# PowerSupply.net
KiCad netlist of a schematic drawn in Altium Designer
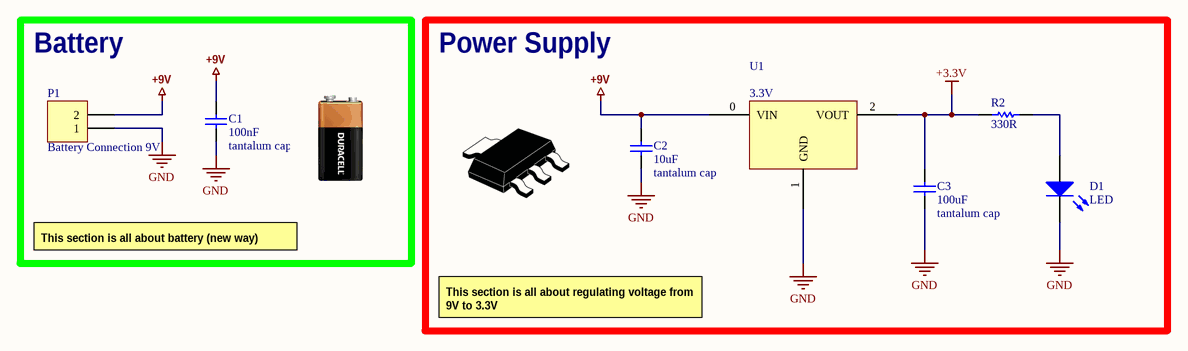
[diagram p0: PowerSupply.SchDoc]

(export (version "E")
  (design (tool "Eeschema 10.0.6"))
  (components
    (comp (ref "C1")
      (value "tantalum cap")
      (footprint "C1206tancap")
      (description "Capacitor (Semiconductor SIM Model)")
      (fields (field (name "ALTIUM_VALUE") "100nF") (field (name "PUBLISHER") "Altium Limited"))
      (libsource (lib "smartmcu") (part "Cap Semi_5"))
    )
    (comp (ref "C2")
      (value "tantalum cap")
      (footprint "C1206tancap")
      (description "Capacitor (Semiconductor SIM Model)")
      (fields (field (name "ALTIUM_VALUE") "10uF") (field (name "PUBLISHER") "Altium Limited"))
      (libsource (lib "smartmcu") (part "Cap Semi_5"))
    )
    (comp (ref "C3")
      (value "tantalum cap")
      (footprint "C1206tancap")
      (description "Capacitor (Semiconductor SIM Model)")
      (fields (field (name "ALTIUM_VALUE") "100uF") (field (name "PUBLISHER") "Altium Limited"))
      (libsource (lib "smartmcu") (part "Cap Semi_6"))
    )
    (comp (ref "D1")
      (value "LED")
      (footprint "MY_LED_0805")
      (description "Typical INFRARED GaAs LED")
      (fields (field (name "ASID PART NUMBER") "LED-AS"))
      (libsource (lib "Mylib+Rev+4") (part "LED"))
    )
    (comp (ref "P1")
      (value "Battery Connection 9V")
      (footprint "HDR1X2H3dbody")
      (description "Header, 2-Pin, Right Angle")
      (fields (field (name "VOLTAGE") "9V") (field (name "PUBLISHER") "Altium Limited"))
      (libsource (lib "smartmcu") (part "Header 2H"))
    )
    (comp (ref "R2")
      (value "330R")
      (footprint "MY_0805")
      (description "Standard resistor")
      (fields (field (name "ASID PART NUMBER") "Res-AS"))
      (libsource (lib "Mylib+Rev+4") (part "Res"))
    )
    (comp (ref "U1")
      (value "~")
      (footprint "4-Pin SOT")
      (fields (field (name "OUTPUT VOLTAGE") "3.3V"))
      (libsource (lib "smartmcu") (part "LM1117"))
    )
  )
  (nets
    (net (code "1") (name "+3.3V") (class "Default")
      (node (ref "C3") (pin "2") (pinfunction "2_2") (pintype "passive"))
      (node (ref "R2") (pin "1") (pinfunction "1_1") (pintype "passive"))
      (node (ref "U1") (pin "2") (pinfunction "VOUT_2") (pintype "passive"))
    )
    (net (code "2") (name "+9V") (class "Default")
      (node (ref "C1") (pin "2") (pinfunction "2_2") (pintype "passive"))
      (node (ref "C2") (pin "2") (pinfunction "2_2") (pintype "passive"))
      (node (ref "P1") (pin "2") (pinfunction "2_2") (pintype "passive"))
      (node (ref "U1") (pin "0") (pinfunction "VIN_0") (pintype "passive"))
    )
    (net (code "3") (name "GND") (class "Default")
      (node (ref "C1") (pin "1") (pinfunction "1_1") (pintype "passive"))
      (node (ref "C2") (pin "1") (pinfunction "1_1") (pintype "passive"))
      (node (ref "C3") (pin "1") (pinfunction "1_1") (pintype "passive"))
      (node (ref "D1") (pin "K") (pinfunction "K_K") (pintype "passive"))
      (node (ref "P1") (pin "1") (pinfunction "1_1") (pintype "passive"))
      (node (ref "U1") (pin "1") (pinfunction "GND_1") (pintype "passive"))
    )
    (net (code "4") (name "Net-(D1-PadA)") (class "Default")
      (node (ref "D1") (pin "A") (pinfunction "A_A") (pintype "passive"))
      (node (ref "R2") (pin "2") (pinfunction "2_2") (pintype "passive"))
    )
  )
)
